# 06-General_I2C_Devices.net
KiCad netlist of a schematic drawn in Altium Designer
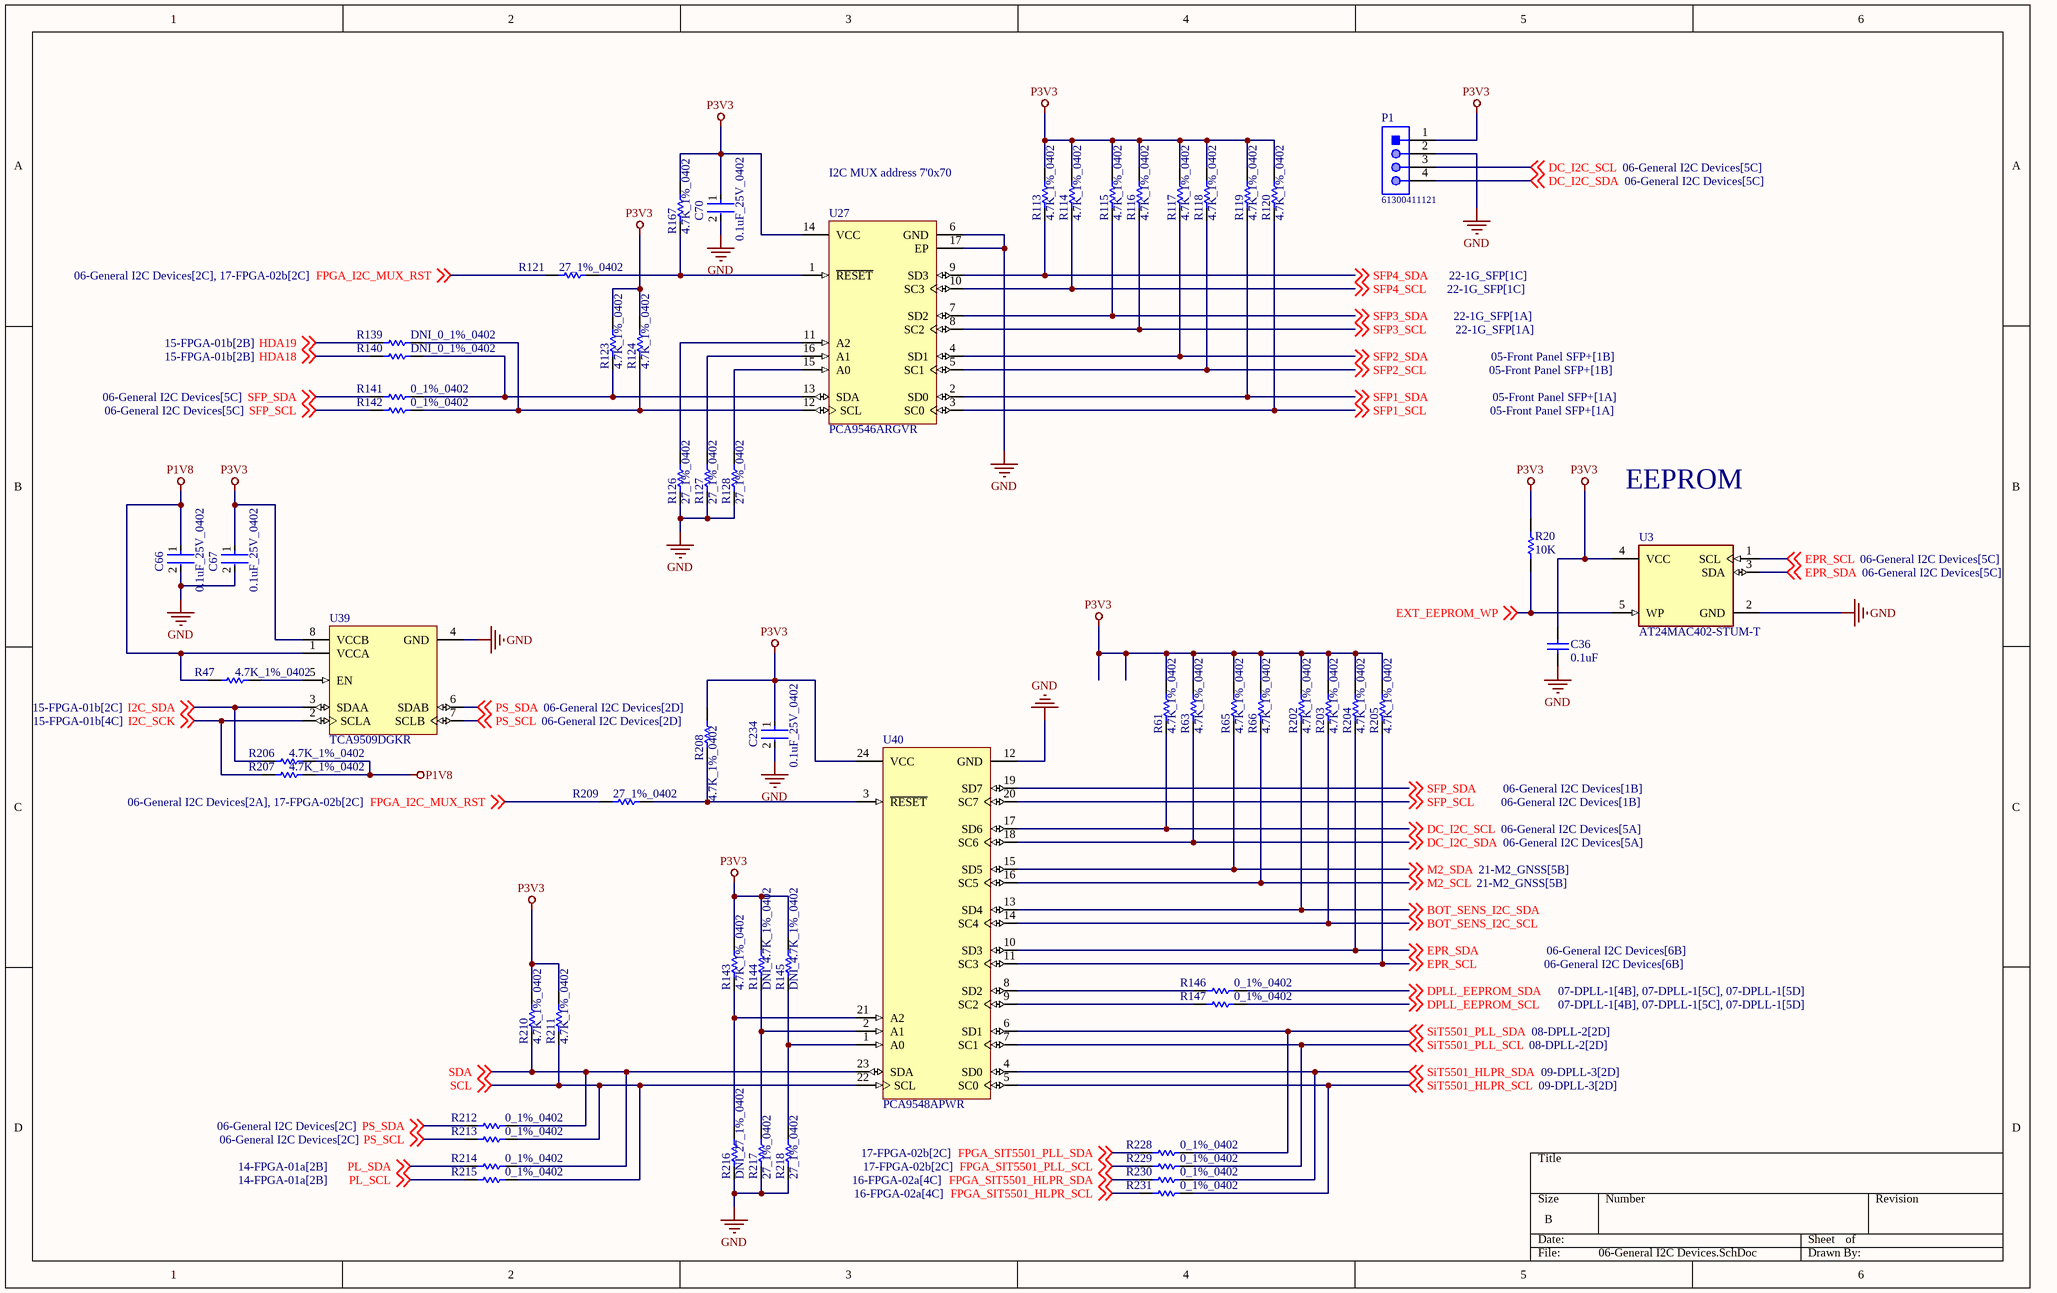
[diagram p0: 06-General I2C Devices.SchDoc]

(export (version "E")
  (design (tool "Eeschema 10.0.6"))
  (components
    (comp (ref "C36")
      (value "0.1uF")
      (footprint "CAPC1608X87X45ML20T05")
      (description "C0603X104K5RACAUTO")
      (fields (field (name "MANUFACTURER") "Kemet"))
      (libsource (lib "Altium Content Vault") (part "CAP"))
    )
    (comp (ref "C66")
      (value "0.1uF_25V_0402")
      (footprint "FP-0402-L_1_0_1-W_0_5_0_1-IPC_C")
      (description "General Purpose Ceramic Capacitor, 0402, 100nF, 10%, X7R, 15%, 25V")
      (fields (field (name "VOLTAGE") "25V") (field (name "TOLERANCE") "10%"))
      (libsource (lib "Altium Content Vault") (part "b4654b650e69147ec39a6b967a45e02"))
    )
    (comp (ref "C67")
      (value "0.1uF_25V_0402")
      (footprint "FP-0402-L_1_0_1-W_0_5_0_1-IPC_C")
      (description "General Purpose Ceramic Capacitor, 0402, 100nF, 10%, X7R, 15%, 25V")
      (fields (field (name "VOLTAGE") "25V") (field (name "TOLERANCE") "10%"))
      (libsource (lib "Altium Content Vault") (part "b4654b650e69147ec39a6b967a45e02"))
    )
    (comp (ref "C70")
      (value "0.1uF_25V_0402")
      (footprint "FP-0402-L_1_0_1-W_0_5_0_1-IPC_C")
      (description "General Purpose Ceramic Capacitor, 0402, 100nF, 10%, X7R, 15%, 25V")
      (fields (field (name "VOLTAGE") "25V") (field (name "TOLERANCE") "10%"))
      (libsource (lib "Altium Content Vault") (part "b4654b650e69147ec39a6b967a45e02"))
    )
    (comp (ref "C234")
      (value "0.1uF_25V_0402")
      (footprint "FP-0402-L_1_0_1-W_0_5_0_1-IPC_C")
      (description "General Purpose Ceramic Capacitor, 0402, 100nF, 10%, X7R, 15%, 25V")
      (fields (field (name "VOLTAGE") "25V") (field (name "TOLERANCE") "10%"))
      (libsource (lib "Altium Content Vault") (part "b4654b650e69147ec39a6b967a45e02"))
    )
    (comp (ref "P1")
      (value "61300411121")
      (footprint "61300411121")
      (description "THT Vertical Pin Header WR-PHD, Pitch 2.54 mm, Single Row, 4 pins")
      (fields (field (name "MANUFACTURER") "Wurth Elektronik") (field (name "PUBLISHER") "WurthElektronik"))
      (libsource (lib "Altium Content Vault") (part "WE-CN-1P-M-R4"))
    )
    (comp (ref "R20")
      (value "10K")
      (footprint "RESC1608X55X30LL15T20")
      (fields (field (name "TOLERANCE") "±1%") (field (name "MANUFACTURER") "Stackpole-Electronics-Inc."))
      (libsource (lib "Altium Content Vault") (part "RES-2"))
    )
    (comp (ref "R47")
      (value "4.7K_1%_0402")
      (footprint "RESC1005X40X25NL10T10")
      (fields (field (name "MANUFACTURER") "Bourns") (field (name "PART NUMBER") "CR0402-FX-4701GLF"))
      (libsource (lib "Altium Content Vault") (part "RES"))
    )
    (comp (ref "R61")
      (value "4.7K_1%_0402")
      (footprint "RESC1005X40X25NL10T10")
      (fields (field (name "MANUFACTURER") "Bourns") (field (name "PART NUMBER") "CR0402-FX-4701GLF"))
      (libsource (lib "Altium Content Vault") (part "RES"))
    )
    (comp (ref "R63")
      (value "4.7K_1%_0402")
      (footprint "RESC1005X40X25NL10T10")
      (fields (field (name "MANUFACTURER") "Bourns") (field (name "PART NUMBER") "CR0402-FX-4701GLF"))
      (libsource (lib "Altium Content Vault") (part "RES"))
    )
    (comp (ref "R65")
      (value "4.7K_1%_0402")
      (footprint "RESC1005X40X25NL10T10")
      (fields (field (name "MANUFACTURER") "Bourns") (field (name "PART NUMBER") "CR0402-FX-4701GLF"))
      (libsource (lib "Altium Content Vault") (part "RES"))
    )
    (comp (ref "R66")
      (value "4.7K_1%_0402")
      (footprint "RESC1005X40X25NL10T10")
      (fields (field (name "MANUFACTURER") "Bourns") (field (name "PART NUMBER") "CR0402-FX-4701GLF"))
      (libsource (lib "Altium Content Vault") (part "RES"))
    )
    (comp (ref "R113")
      (value "4.7K_1%_0402")
      (footprint "RESC1005X40X25NL10T10")
      (fields (field (name "MANUFACTURER") "Bourns") (field (name "PART NUMBER") "CR0402-FX-4701GLF"))
      (libsource (lib "Altium Content Vault") (part "RES"))
    )
    (comp (ref "R114")
      (value "4.7K_1%_0402")
      (footprint "RESC1005X40X25NL10T10")
      (fields (field (name "MANUFACTURER") "Bourns") (field (name "PART NUMBER") "CR0402-FX-4701GLF"))
      (libsource (lib "Altium Content Vault") (part "RES"))
    )
    (comp (ref "R115")
      (value "4.7K_1%_0402")
      (footprint "RESC1005X40X25NL10T10")
      (fields (field (name "MANUFACTURER") "Bourns") (field (name "PART NUMBER") "CR0402-FX-4701GLF"))
      (libsource (lib "Altium Content Vault") (part "RES"))
    )
    (comp (ref "R116")
      (value "4.7K_1%_0402")
      (footprint "RESC1005X40X25NL10T10")
      (fields (field (name "MANUFACTURER") "Bourns") (field (name "PART NUMBER") "CR0402-FX-4701GLF"))
      (libsource (lib "Altium Content Vault") (part "RES"))
    )
    (comp (ref "R117")
      (value "4.7K_1%_0402")
      (footprint "RESC1005X40X25NL10T10")
      (fields (field (name "MANUFACTURER") "Bourns") (field (name "PART NUMBER") "CR0402-FX-4701GLF"))
      (libsource (lib "Altium Content Vault") (part "RES"))
    )
    (comp (ref "R118")
      (value "4.7K_1%_0402")
      (footprint "RESC1005X40X25NL10T10")
      (fields (field (name "MANUFACTURER") "Bourns") (field (name "PART NUMBER") "CR0402-FX-4701GLF"))
      (libsource (lib "Altium Content Vault") (part "RES"))
    )
    (comp (ref "R119")
      (value "4.7K_1%_0402")
      (footprint "RESC1005X40X25NL10T10")
      (fields (field (name "MANUFACTURER") "Bourns") (field (name "PART NUMBER") "CR0402-FX-4701GLF"))
      (libsource (lib "Altium Content Vault") (part "RES"))
    )
    (comp (ref "R120")
      (value "4.7K_1%_0402")
      (footprint "RESC1005X40X25NL10T10")
      (fields (field (name "MANUFACTURER") "Bourns") (field (name "PART NUMBER") "CR0402-FX-4701GLF"))
      (libsource (lib "Altium Content Vault") (part "RES"))
    )
    (comp (ref "R121")
      (value "27_1%_0402")
      (footprint "RESC1005X40X25NL05T05")
      (fields (field (name "PART NUMBER") "CRCW040227R0FKED") (field (name "MANUFACTURER") "Vishay Dale"))
      (libsource (lib "Altium Content Vault") (part "RES"))
    )
    (comp (ref "R123")
      (value "4.7K_1%_0402")
      (footprint "RESC1005X40X25NL10T10")
      (fields (field (name "MANUFACTURER") "Bourns") (field (name "PART NUMBER") "CR0402-FX-4701GLF"))
      (libsource (lib "Altium Content Vault") (part "RES"))
    )
    (comp (ref "R124")
      (value "4.7K_1%_0402")
      (footprint "RESC1005X40X25NL10T10")
      (fields (field (name "MANUFACTURER") "Bourns") (field (name "PART NUMBER") "CR0402-FX-4701GLF"))
      (libsource (lib "Altium Content Vault") (part "RES"))
    )
    (comp (ref "R126")
      (value "27_1%_0402")
      (footprint "RESC1005X40X25NL05T05")
      (fields (field (name "PART NUMBER") "CRCW040227R0FKED") (field (name "MANUFACTURER") "Vishay Dale"))
      (libsource (lib "Altium Content Vault") (part "RES"))
    )
    (comp (ref "R127")
      (value "27_1%_0402")
      (footprint "RESC1005X40X25NL05T05")
      (fields (field (name "PART NUMBER") "CRCW040227R0FKED") (field (name "MANUFACTURER") "Vishay Dale"))
      (libsource (lib "Altium Content Vault") (part "RES"))
    )
    (comp (ref "R128")
      (value "27_1%_0402")
      (footprint "RESC1005X40X25NL05T05")
      (fields (field (name "PART NUMBER") "CRCW040227R0FKED") (field (name "MANUFACTURER") "Vishay Dale"))
      (libsource (lib "Altium Content Vault") (part "RES"))
    )
    (comp (ref "R139")
      (value "DNI_0_1%_0402")
      (footprint "RESC1005X40X25LL05T05")
      (description "Chip Resistor, 0 Ohm, 0.1 W, -55 to 155 degC, 0402 (1005 Metric), RoHS, Tape and Reel")
      (fields (field (name "MANUFACTURER") "Panasonic") (field (name "TOLERANCE") "5%"))
      (libsource (lib "Altium Content Vault") (part "RES-2"))
    )
    (comp (ref "R140")
      (value "DNI_0_1%_0402")
      (footprint "RESC1005X40X25LL05T05")
      (description "Chip Resistor, 0 Ohm, 0.1 W, -55 to 155 degC, 0402 (1005 Metric), RoHS, Tape and Reel")
      (fields (field (name "MANUFACTURER") "Panasonic") (field (name "TOLERANCE") "5%"))
      (libsource (lib "Altium Content Vault") (part "RES-2"))
    )
    (comp (ref "R141")
      (value "0_1%_0402")
      (footprint "RESC1005X40X25LL05T05")
      (description "Chip Resistor, 0 Ohm, 0.1 W, -55 to 155 degC, 0402 (1005 Metric), RoHS, Tape and Reel")
      (fields (field (name "MANUFACTURER") "Panasonic") (field (name "TOLERANCE") "5%"))
      (libsource (lib "Altium Content Vault") (part "RES-2"))
    )
    (comp (ref "R142")
      (value "0_1%_0402")
      (footprint "RESC1005X40X25LL05T05")
      (description "Chip Resistor, 0 Ohm, 0.1 W, -55 to 155 degC, 0402 (1005 Metric), RoHS, Tape and Reel")
      (fields (field (name "MANUFACTURER") "Panasonic") (field (name "TOLERANCE") "5%"))
      (libsource (lib "Altium Content Vault") (part "RES-2"))
    )
    (comp (ref "R143")
      (value "4.7K_1%_0402")
      (footprint "RESC1005X40X25NL10T10")
      (fields (field (name "MANUFACTURER") "Bourns") (field (name "PART NUMBER") "CR0402-FX-4701GLF"))
      (libsource (lib "Altium Content Vault") (part "RES"))
    )
    (comp (ref "R144")
      (value "DNI_4.7K_1%_0402")
      (footprint "RESC1005X40X25NL10T10")
      (fields (field (name "MANUFACTURER") "Bourns") (field (name "PART NUMBER") "CR0402-FX-4701GLF"))
      (libsource (lib "Altium Content Vault") (part "RES"))
    )
    (comp (ref "R145")
      (value "DNI_4.7K_1%_0402")
      (footprint "RESC1005X40X25NL10T10")
      (fields (field (name "MANUFACTURER") "Bourns") (field (name "PART NUMBER") "CR0402-FX-4701GLF"))
      (libsource (lib "Altium Content Vault") (part "RES"))
    )
    (comp (ref "R146")
      (value "0_1%_0402")
      (footprint "RESC1005X40X25LL05T05")
      (description "Chip Resistor, 0 Ohm, 0.1 W, -55 to 155 degC, 0402 (1005 Metric), RoHS, Tape and Reel")
      (fields (field (name "MANUFACTURER") "Panasonic") (field (name "TOLERANCE") "5%"))
      (libsource (lib "Altium Content Vault") (part "RES-2"))
    )
    (comp (ref "R147")
      (value "0_1%_0402")
      (footprint "RESC1005X40X25LL05T05")
      (description "Chip Resistor, 0 Ohm, 0.1 W, -55 to 155 degC, 0402 (1005 Metric), RoHS, Tape and Reel")
      (fields (field (name "MANUFACTURER") "Panasonic") (field (name "TOLERANCE") "5%"))
      (libsource (lib "Altium Content Vault") (part "RES-2"))
    )
    (comp (ref "R167")
      (value "4.7K_1%_0402")
      (footprint "RESC1005X40X25NL10T10")
      (fields (field (name "MANUFACTURER") "Bourns") (field (name "PART NUMBER") "CR0402-FX-4701GLF"))
      (libsource (lib "Altium Content Vault") (part "RES"))
    )
    (comp (ref "R202")
      (value "4.7K_1%_0402")
      (footprint "RESC1005X40X25NL10T10")
      (fields (field (name "MANUFACTURER") "Bourns") (field (name "PART NUMBER") "CR0402-FX-4701GLF"))
      (libsource (lib "Altium Content Vault") (part "RES"))
    )
    (comp (ref "R203")
      (value "4.7K_1%_0402")
      (footprint "RESC1005X40X25NL10T10")
      (fields (field (name "MANUFACTURER") "Bourns") (field (name "PART NUMBER") "CR0402-FX-4701GLF"))
      (libsource (lib "Altium Content Vault") (part "RES"))
    )
    (comp (ref "R204")
      (value "4.7K_1%_0402")
      (footprint "RESC1005X40X25NL10T10")
      (fields (field (name "MANUFACTURER") "Bourns") (field (name "PART NUMBER") "CR0402-FX-4701GLF"))
      (libsource (lib "Altium Content Vault") (part "RES"))
    )
    (comp (ref "R205")
      (value "4.7K_1%_0402")
      (footprint "RESC1005X40X25NL10T10")
      (fields (field (name "MANUFACTURER") "Bourns") (field (name "PART NUMBER") "CR0402-FX-4701GLF"))
      (libsource (lib "Altium Content Vault") (part "RES"))
    )
    (comp (ref "R206")
      (value "4.7K_1%_0402")
      (footprint "RESC1005X40X25NL10T10")
      (fields (field (name "MANUFACTURER") "Bourns") (field (name "PART NUMBER") "CR0402-FX-4701GLF"))
      (libsource (lib "Altium Content Vault") (part "RES"))
    )
    (comp (ref "R207")
      (value "4.7K_1%_0402")
      (footprint "RESC1005X40X25NL10T10")
      (fields (field (name "MANUFACTURER") "Bourns") (field (name "PART NUMBER") "CR0402-FX-4701GLF"))
      (libsource (lib "Altium Content Vault") (part "RES"))
    )
    (comp (ref "R208")
      (value "4.7K_1%_0402")
      (footprint "RESC1005X40X25NL10T10")
      (fields (field (name "MANUFACTURER") "Bourns") (field (name "PART NUMBER") "CR0402-FX-4701GLF"))
      (libsource (lib "Altium Content Vault") (part "RES"))
    )
    (comp (ref "R209")
      (value "27_1%_0402")
      (footprint "RESC1005X40X25NL05T05")
      (fields (field (name "PART NUMBER") "CRCW040227R0FKED") (field (name "MANUFACTURER") "Vishay Dale"))
      (libsource (lib "Altium Content Vault") (part "RES"))
    )
    (comp (ref "R210")
      (value "4.7K_1%_0402")
      (footprint "RESC1005X40X25NL10T10")
      (fields (field (name "MANUFACTURER") "Bourns") (field (name "PART NUMBER") "CR0402-FX-4701GLF"))
      (libsource (lib "Altium Content Vault") (part "RES"))
    )
    (comp (ref "R211")
      (value "4.7K_1%_0402")
      (footprint "RESC1005X40X25NL10T10")
      (fields (field (name "MANUFACTURER") "Bourns") (field (name "PART NUMBER") "CR0402-FX-4701GLF"))
      (libsource (lib "Altium Content Vault") (part "RES"))
    )
    (comp (ref "R212")
      (value "0_1%_0402")
      (footprint "RESC1005X40X25LL05T05")
      (description "Chip Resistor, 0 Ohm, 0.1 W, -55 to 155 degC, 0402 (1005 Metric), RoHS, Tape and Reel")
      (fields (field (name "MANUFACTURER") "Panasonic") (field (name "TOLERANCE") "5%"))
      (libsource (lib "Altium Content Vault") (part "RES-2"))
    )
    (comp (ref "R213")
      (value "0_1%_0402")
      (footprint "RESC1005X40X25LL05T05")
      (description "Chip Resistor, 0 Ohm, 0.1 W, -55 to 155 degC, 0402 (1005 Metric), RoHS, Tape and Reel")
      (fields (field (name "MANUFACTURER") "Panasonic") (field (name "TOLERANCE") "5%"))
      (libsource (lib "Altium Content Vault") (part "RES-2"))
    )
    (comp (ref "R214")
      (value "0_1%_0402")
      (footprint "RESC1005X40X25LL05T05")
      (description "Chip Resistor, 0 Ohm, 0.1 W, -55 to 155 degC, 0402 (1005 Metric), RoHS, Tape and Reel")
      (fields (field (name "MANUFACTURER") "Panasonic") (field (name "TOLERANCE") "5%"))
      (libsource (lib "Altium Content Vault") (part "RES-2"))
    )
    (comp (ref "R215")
      (value "0_1%_0402")
      (footprint "RESC1005X40X25LL05T05")
      (description "Chip Resistor, 0 Ohm, 0.1 W, -55 to 155 degC, 0402 (1005 Metric), RoHS, Tape and Reel")
      (fields (field (name "MANUFACTURER") "Panasonic") (field (name "TOLERANCE") "5%"))
      (libsource (lib "Altium Content Vault") (part "RES-2"))
    )
    (comp (ref "R216")
      (value "DNI_27_1%_0402")
      (footprint "RESC1005X40X25NL05T05")
      (fields (field (name "PART NUMBER") "CRCW040227R0FKED") (field (name "MANUFACTURER") "Vishay Dale"))
      (libsource (lib "Altium Content Vault") (part "RES"))
    )
    (comp (ref "R217")
      (value "27_1%_0402")
      (footprint "RESC1005X40X25NL05T05")
      (fields (field (name "PART NUMBER") "CRCW040227R0FKED") (field (name "MANUFACTURER") "Vishay Dale"))
      (libsource (lib "Altium Content Vault") (part "RES"))
    )
    (comp (ref "R218")
      (value "27_1%_0402")
      (footprint "RESC1005X40X25NL05T05")
      (fields (field (name "PART NUMBER") "CRCW040227R0FKED") (field (name "MANUFACTURER") "Vishay Dale"))
      (libsource (lib "Altium Content Vault") (part "RES"))
    )
    (comp (ref "R228")
      (value "0_1%_0402")
      (footprint "RESC1005X40X25LL05T05")
      (description "Chip Resistor, 0 Ohm, 0.1 W, -55 to 155 degC, 0402 (1005 Metric), RoHS, Tape and Reel")
      (fields (field (name "MANUFACTURER") "Panasonic") (field (name "TOLERANCE") "5%"))
      (libsource (lib "Altium Content Vault") (part "RES-2"))
    )
    (comp (ref "R229")
      (value "0_1%_0402")
      (footprint "RESC1005X40X25LL05T05")
      (description "Chip Resistor, 0 Ohm, 0.1 W, -55 to 155 degC, 0402 (1005 Metric), RoHS, Tape and Reel")
      (fields (field (name "MANUFACTURER") "Panasonic") (field (name "TOLERANCE") "5%"))
      (libsource (lib "Altium Content Vault") (part "RES-2"))
    )
    (comp (ref "R230")
      (value "0_1%_0402")
      (footprint "RESC1005X40X25LL05T05")
      (description "Chip Resistor, 0 Ohm, 0.1 W, -55 to 155 degC, 0402 (1005 Metric), RoHS, Tape and Reel")
      (fields (field (name "MANUFACTURER") "Panasonic") (field (name "TOLERANCE") "5%"))
      (libsource (lib "Altium Content Vault") (part "RES-2"))
    )
    (comp (ref "R231")
      (value "0_1%_0402")
      (footprint "RESC1005X40X25LL05T05")
      (description "Chip Resistor, 0 Ohm, 0.1 W, -55 to 155 degC, 0402 (1005 Metric), RoHS, Tape and Reel")
      (fields (field (name "MANUFACTURER") "Panasonic") (field (name "TOLERANCE") "5%"))
      (libsource (lib "Altium Content Vault") (part "RES-2"))
    )
    (comp (ref "U3")
      (value "AT24MAC402-STUM-T")
      (footprint "FP-5TS1-IPC_C")
      (description "IC EEPROM 2K I2C 1MHZ SOT23-5")
      (fields
        (field (name "MANUFACTURER") "Microchip")
        (field (name "OCTOPART") "https://octopart.com/at24mac402-stum-t-microchip-77758112")
      )
      (libsource (lib "Altium Content Vault") (part "93fe34f5f049140596bab6421a6454b"))
    )
    (comp (ref "U27")
      (value "PCA9546ARGVR")
      (footprint "RGV0016A_V")
      (fields (field (name "MANUFACTURER") "Texas Instruments"))
      (libsource (lib "Altium Content Vault") (part "TI-PCA9546A-VQFN_RGV-16"))
    )
    (comp (ref "U39")
      (value "TCA9509DGKR")
      (footprint "DGK0008A_L")
      (fields (field (name "MANUFACTURER") "Texas Instruments"))
      (libsource (lib "Altium Content Vault") (part "TI-TCA9509-MSOP_DGK-8"))
    )
    (comp (ref "U40")
      (value "PCA9548APWR")
      (footprint "PW0024A_N")
      (fields (field (name "MANUFACTURER") "Texas Instruments"))
      (libsource (lib "Altium Content Vault") (part "TI-PCA9548A-TSSOP_PW-24"))
    )
  )
  (nets
    (net (code "1") (name "BOT_SENS_I2C_SCL") (class "Default")
      (node (ref "R203") (pin "1") (pinfunction "1_1") (pintype "passive"))
      (node (ref "U40") (pin "14") (pinfunction "SC4_14") (pintype "bidirectional"))
    )
    (net (code "2") (name "BOT_SENS_I2C_SDA") (class "Default")
      (node (ref "R202") (pin "1") (pinfunction "1_1") (pintype "passive"))
      (node (ref "U40") (pin "13") (pinfunction "SD4_13") (pintype "bidirectional"))
    )
    (net (code "3") (name "DC_I2C_SCL") (class "Default")
      (node (ref "P1") (pin "3") (pinfunction "3_3") (pintype "passive"))
      (node (ref "R61") (pin "1") (pinfunction "1_1") (pintype "passive"))
      (node (ref "U40") (pin "17") (pinfunction "SD6_17") (pintype "bidirectional"))
    )
    (net (code "4") (name "DC_I2C_SDA") (class "Default")
      (node (ref "P1") (pin "4") (pinfunction "4_4") (pintype "passive"))
      (node (ref "R63") (pin "1") (pinfunction "1_1") (pintype "passive"))
      (node (ref "U40") (pin "18") (pinfunction "SC6_18") (pintype "bidirectional"))
    )
    (net (code "5") (name "DPLL_EEPROM_SCL") (class "Default")
      (node (ref "R147") (pin "2") (pinfunction "2_2") (pintype "passive"))
    )
    (net (code "6") (name "DPLL_EEPROM_SDA") (class "Default")
      (node (ref "R146") (pin "2") (pinfunction "2_2") (pintype "passive"))
    )
    (net (code "7") (name "EPR_SCL") (class "Default")
      (node (ref "R205") (pin "1") (pinfunction "1_1") (pintype "passive"))
      (node (ref "U3") (pin "1") (pinfunction "SCL_1") (pintype "input"))
      (node (ref "U40") (pin "11") (pinfunction "SC3_11") (pintype "bidirectional"))
    )
    (net (code "8") (name "EPR_SDA") (class "Default")
      (node (ref "R204") (pin "1") (pinfunction "1_1") (pintype "passive"))
      (node (ref "U3") (pin "3") (pinfunction "SDA_3") (pintype "bidirectional"))
      (node (ref "U40") (pin "10") (pinfunction "SD3_10") (pintype "bidirectional"))
    )
    (net (code "9") (name "EXT_EEPROM_WP") (class "Default")
      (node (ref "R20") (pin "1") (pinfunction "1_1") (pintype "passive"))
      (node (ref "U3") (pin "5") (pinfunction "WP_5") (pintype "input"))
    )
    (net (code "10") (name "FPGA_I2C_MUX_RST") (class "Default")
      (node (ref "R121") (pin "1") (pinfunction "1_1") (pintype "passive"))
      (node (ref "R209") (pin "1") (pinfunction "1_1") (pintype "passive"))
    )
    (net (code "11") (name "FPGA_SIT5501_HLPR_SCL") (class "Default")
      (node (ref "R231") (pin "1") (pinfunction "1_1") (pintype "passive"))
    )
    (net (code "12") (name "FPGA_SIT5501_HLPR_SDA") (class "Default")
      (node (ref "R230") (pin "1") (pinfunction "1_1") (pintype "passive"))
    )
    (net (code "13") (name "FPGA_SIT5501_PLL_SCL") (class "Default")
      (node (ref "R229") (pin "1") (pinfunction "1_1") (pintype "passive"))
    )
    (net (code "14") (name "FPGA_SIT5501_PLL_SDA") (class "Default")
      (node (ref "R228") (pin "1") (pinfunction "1_1") (pintype "passive"))
    )
    (net (code "15") (name "GND") (class "Default")
      (node (ref "C234") (pin "2") (pinfunction "2_2") (pintype "passive"))
      (node (ref "C36") (pin "1") (pinfunction "1_1") (pintype "passive"))
      (node (ref "C66") (pin "2") (pinfunction "2_2") (pintype "passive"))
      (node (ref "C67") (pin "2") (pinfunction "2_2") (pintype "passive"))
      (node (ref "C70") (pin "2") (pinfunction "2_2") (pintype "passive"))
      (node (ref "P1") (pin "2") (pinfunction "2_2") (pintype "passive"))
      (node (ref "R126") (pin "1") (pinfunction "1_1") (pintype "passive"))
      (node (ref "R127") (pin "1") (pinfunction "1_1") (pintype "passive"))
      (node (ref "R128") (pin "1") (pinfunction "1_1") (pintype "passive"))
      (node (ref "R216") (pin "1") (pinfunction "1_1") (pintype "passive"))
      (node (ref "R217") (pin "1") (pinfunction "1_1") (pintype "passive"))
      (node (ref "R218") (pin "1") (pinfunction "1_1") (pintype "passive"))
      (node (ref "U27") (pin "17") (pinfunction "EP_17") (pintype "passive"))
      (node (ref "U27") (pin "6") (pinfunction "GND_6") (pintype "power_in"))
      (node (ref "U3") (pin "2") (pinfunction "GND_2") (pintype "power_in"))
      (node (ref "U39") (pin "4") (pinfunction "GND_4") (pintype "power_in"))
      (node (ref "U40") (pin "12") (pinfunction "GND_12") (pintype "power_in"))
    )
    (net (code "16") (name "HDA18") (class "Default")
      (node (ref "R140") (pin "1") (pinfunction "1_1") (pintype "passive"))
    )
    (net (code "17") (name "HDA19") (class "Default")
      (node (ref "R139") (pin "1") (pinfunction "1_1") (pintype "passive"))
    )
    (net (code "18") (name "I2C_SCK") (class "Default")
      (node (ref "R207") (pin "2") (pinfunction "2_2") (pintype "passive"))
      (node (ref "U39") (pin "2") (pinfunction "SCLA_2") (pintype "bidirectional"))
    )
    (net (code "19") (name "I2C_SDA") (class "Default")
      (node (ref "R206") (pin "2") (pinfunction "2_2") (pintype "passive"))
      (node (ref "U39") (pin "3") (pinfunction "SDAA_3") (pintype "bidirectional"))
    )
    (net (code "20") (name "M2_SCL") (class "Default")
      (node (ref "R66") (pin "1") (pinfunction "1_1") (pintype "passive"))
      (node (ref "U40") (pin "16") (pinfunction "SC5_16") (pintype "bidirectional"))
    )
    (net (code "21") (name "M2_SDA") (class "Default")
      (node (ref "R65") (pin "1") (pinfunction "1_1") (pintype "passive"))
      (node (ref "U40") (pin "15") (pinfunction "SD5_15") (pintype "bidirectional"))
    )
    (net (code "22") (name "Net-(U27-A0)") (class "Default")
      (node (ref "R128") (pin "2") (pinfunction "2_2") (pintype "passive"))
      (node (ref "U27") (pin "15") (pinfunction "A0_15") (pintype "input"))
    )
    (net (code "23") (name "Net-(U27-A1)") (class "Default")
      (node (ref "R127") (pin "2") (pinfunction "2_2") (pintype "passive"))
      (node (ref "U27") (pin "16") (pinfunction "A1_16") (pintype "input"))
    )
    (net (code "24") (name "Net-(U27-A2)") (class "Default")
      (node (ref "R126") (pin "2") (pinfunction "2_2") (pintype "passive"))
      (node (ref "U27") (pin "11") (pinfunction "A2_11") (pintype "input"))
    )
    (net (code "25") (name "Net-(U27-SCL)") (class "Default")
      (node (ref "R124") (pin "1") (pinfunction "1_1") (pintype "passive"))
      (node (ref "R139") (pin "2") (pinfunction "2_2") (pintype "passive"))
      (node (ref "R142") (pin "2") (pinfunction "2_2") (pintype "passive"))
      (node (ref "U27") (pin "12") (pinfunction "SCL_12") (pintype "bidirectional"))
    )
    (net (code "26") (name "Net-(U27-SDA)") (class "Default")
      (node (ref "R123") (pin "1") (pinfunction "1_1") (pintype "passive"))
      (node (ref "R140") (pin "2") (pinfunction "2_2") (pintype "passive"))
      (node (ref "R141") (pin "2") (pinfunction "2_2") (pintype "passive"))
      (node (ref "U27") (pin "13") (pinfunction "SDA_13") (pintype "bidirectional"))
    )
    (net (code "27") (name "Net-(U27-~{RESET})") (class "Default")
      (node (ref "R121") (pin "2") (pinfunction "2_2") (pintype "passive"))
      (node (ref "R167") (pin "1") (pinfunction "1_1") (pintype "passive"))
      (node (ref "U27") (pin "1") (pinfunction "~{RESET}_1") (pintype "input"))
    )
    (net (code "28") (name "Net-(U39-EN)") (class "Default")
      (node (ref "R47") (pin "1") (pinfunction "1_1") (pintype "passive"))
      (node (ref "U39") (pin "5") (pinfunction "EN_5") (pintype "input"))
    )
    (net (code "29") (name "Net-(U40-A0)") (class "Default")
      (node (ref "R145") (pin "1") (pinfunction "1_1") (pintype "passive"))
      (node (ref "R218") (pin "2") (pinfunction "2_2") (pintype "passive"))
      (node (ref "U40") (pin "1") (pinfunction "A0_1") (pintype "input"))
    )
    (net (code "30") (name "Net-(U40-A1)") (class "Default")
      (node (ref "R144") (pin "1") (pinfunction "1_1") (pintype "passive"))
      (node (ref "R217") (pin "2") (pinfunction "2_2") (pintype "passive"))
      (node (ref "U40") (pin "2") (pinfunction "A1_2") (pintype "input"))
    )
    (net (code "31") (name "Net-(U40-A2)") (class "Default")
      (node (ref "R143") (pin "1") (pinfunction "1_1") (pintype "passive"))
      (node (ref "R216") (pin "2") (pinfunction "2_2") (pintype "passive"))
      (node (ref "U40") (pin "21") (pinfunction "A2_21") (pintype "input"))
    )
    (net (code "32") (name "Net-(U40-SC2)") (class "Default")
      (node (ref "R147") (pin "1") (pinfunction "1_1") (pintype "passive"))
      (node (ref "U40") (pin "9") (pinfunction "SC2_9") (pintype "bidirectional"))
    )
    (net (code "33") (name "Net-(U40-SD2)") (class "Default")
      (node (ref "R146") (pin "1") (pinfunction "1_1") (pintype "passive"))
      (node (ref "U40") (pin "8") (pinfunction "SD2_8") (pintype "bidirectional"))
    )
    (net (code "34") (name "Net-(U40-~{RESET})") (class "Default")
      (node (ref "R208") (pin "1") (pinfunction "1_1") (pintype "passive"))
      (node (ref "R209") (pin "2") (pinfunction "2_2") (pintype "passive"))
      (node (ref "U40") (pin "3") (pinfunction "~{RESET}_3") (pintype "input"))
    )
    (net (code "35") (name "P1V8") (class "Default")
      (node (ref "C66") (pin "1") (pinfunction "1_1") (pintype "passive"))
      (node (ref "R206") (pin "1") (pinfunction "1_1") (pintype "passive"))
      (node (ref "R207") (pin "1") (pinfunction "1_1") (pintype "passive"))
      (node (ref "R47") (pin "2") (pinfunction "2_2") (pintype "passive"))
      (node (ref "U39") (pin "1") (pinfunction "VCCA_1") (pintype "power_in"))
    )
    (net (code "36") (name "P3V3") (class "Default")
      (node (ref "C234") (pin "1") (pinfunction "1_1") (pintype "passive"))
      (node (ref "C36") (pin "2") (pinfunction "2_2") (pintype "passive"))
      (node (ref "C67") (pin "1") (pinfunction "1_1") (pintype "passive"))
      (node (ref "C70") (pin "1") (pinfunction "1_1") (pintype "passive"))
      (node (ref "P1") (pin "1") (pinfunction "1_1") (pintype "passive"))
      (node (ref "R113") (pin "2") (pinfunction "2_2") (pintype "passive"))
      (node (ref "R114") (pin "2") (pinfunction "2_2") (pintype "passive"))
      (node (ref "R115") (pin "2") (pinfunction "2_2") (pintype "passive"))
      (node (ref "R116") (pin "2") (pinfunction "2_2") (pintype "passive"))
      (node (ref "R117") (pin "2") (pinfunction "2_2") (pintype "passive"))
      (node (ref "R118") (pin "2") (pinfunction "2_2") (pintype "passive"))
      (node (ref "R119") (pin "2") (pinfunction "2_2") (pintype "passive"))
      (node (ref "R120") (pin "2") (pinfunction "2_2") (pintype "passive"))
      (node (ref "R123") (pin "2") (pinfunction "2_2") (pintype "passive"))
      (node (ref "R124") (pin "2") (pinfunction "2_2") (pintype "passive"))
      (node (ref "R143") (pin "2") (pinfunction "2_2") (pintype "passive"))
      (node (ref "R144") (pin "2") (pinfunction "2_2") (pintype "passive"))
      (node (ref "R145") (pin "2") (pinfunction "2_2") (pintype "passive"))
      (node (ref "R167") (pin "2") (pinfunction "2_2") (pintype "passive"))
      (node (ref "R20") (pin "2") (pinfunction "2_2") (pintype "passive"))
      (node (ref "R202") (pin "2") (pinfunction "2_2") (pintype "passive"))
      (node (ref "R203") (pin "2") (pinfunction "2_2") (pintype "passive"))
      (node (ref "R204") (pin "2") (pinfunction "2_2") (pintype "passive"))
      (node (ref "R205") (pin "2") (pinfunction "2_2") (pintype "passive"))
      (node (ref "R208") (pin "2") (pinfunction "2_2") (pintype "passive"))
      (node (ref "R210") (pin "2") (pinfunction "2_2") (pintype "passive"))
      (node (ref "R211") (pin "2") (pinfunction "2_2") (pintype "passive"))
      (node (ref "R61") (pin "2") (pinfunction "2_2") (pintype "passive"))
      (node (ref "R63") (pin "2") (pinfunction "2_2") (pintype "passive"))
      (node (ref "R65") (pin "2") (pinfunction "2_2") (pintype "passive"))
      (node (ref "R66") (pin "2") (pinfunction "2_2") (pintype "passive"))
      (node (ref "U27") (pin "14") (pinfunction "VCC_14") (pintype "power_in"))
      (node (ref "U3") (pin "4") (pinfunction "VCC_4") (pintype "power_in"))
      (node (ref "U39") (pin "8") (pinfunction "VCCB_8") (pintype "power_in"))
      (node (ref "U40") (pin "24") (pinfunction "VCC_24") (pintype "power_in"))
    )
    (net (code "37") (name "PL_SCL") (class "Default")
      (node (ref "R215") (pin "1") (pinfunction "1_1") (pintype "passive"))
    )
    (net (code "38") (name "PL_SDA") (class "Default")
      (node (ref "R214") (pin "1") (pinfunction "1_1") (pintype "passive"))
    )
    (net (code "39") (name "PS_SCL") (class "Default")
      (node (ref "R213") (pin "1") (pinfunction "1_1") (pintype "passive"))
      (node (ref "U39") (pin "7") (pinfunction "SCLB_7") (pintype "bidirectional"))
    )
    (net (code "40") (name "PS_SDA") (class "Default")
      (node (ref "R212") (pin "1") (pinfunction "1_1") (pintype "passive"))
      (node (ref "U39") (pin "6") (pinfunction "SDAB_6") (pintype "bidirectional"))
    )
    (net (code "41") (name "SCL") (class "Default")
      (node (ref "R211") (pin "1") (pinfunction "1_1") (pintype "passive"))
      (node (ref "R213") (pin "2") (pinfunction "2_2") (pintype "passive"))
      (node (ref "R215") (pin "2") (pinfunction "2_2") (pintype "passive"))
      (node (ref "U40") (pin "22") (pinfunction "SCL_22") (pintype "input"))
    )
    (net (code "42") (name "SDA") (class "Default")
      (node (ref "R210") (pin "1") (pinfunction "1_1") (pintype "passive"))
      (node (ref "R212") (pin "2") (pinfunction "2_2") (pintype "passive"))
      (node (ref "R214") (pin "2") (pinfunction "2_2") (pintype "passive"))
      (node (ref "U40") (pin "23") (pinfunction "SDA_23") (pintype "bidirectional"))
    )
    (net (code "43") (name "SFP1_SCL") (class "Default")
      (node (ref "R120") (pin "1") (pinfunction "1_1") (pintype "passive"))
      (node (ref "U27") (pin "3") (pinfunction "SC0_3") (pintype "bidirectional"))
    )
    (net (code "44") (name "SFP1_SDA") (class "Default")
      (node (ref "R119") (pin "1") (pinfunction "1_1") (pintype "passive"))
      (node (ref "U27") (pin "2") (pinfunction "SD0_2") (pintype "bidirectional"))
    )
    (net (code "45") (name "SFP2_SCL") (class "Default")
      (node (ref "R118") (pin "1") (pinfunction "1_1") (pintype "passive"))
      (node (ref "U27") (pin "5") (pinfunction "SC1_5") (pintype "bidirectional"))
    )
    (net (code "46") (name "SFP2_SDA") (class "Default")
      (node (ref "R117") (pin "1") (pinfunction "1_1") (pintype "passive"))
      (node (ref "U27") (pin "4") (pinfunction "SD1_4") (pintype "bidirectional"))
    )
    (net (code "47") (name "SFP3_SCL") (class "Default")
      (node (ref "R116") (pin "1") (pinfunction "1_1") (pintype "passive"))
      (node (ref "U27") (pin "8") (pinfunction "SC2_8") (pintype "bidirectional"))
    )
    (net (code "48") (name "SFP3_SDA") (class "Default")
      (node (ref "R115") (pin "1") (pinfunction "1_1") (pintype "passive"))
      (node (ref "U27") (pin "7") (pinfunction "SD2_7") (pintype "bidirectional"))
    )
    (net (code "49") (name "SFP4_SCL") (class "Default")
      (node (ref "R114") (pin "1") (pinfunction "1_1") (pintype "passive"))
      (node (ref "U27") (pin "10") (pinfunction "SC3_10") (pintype "bidirectional"))
    )
    (net (code "50") (name "SFP4_SDA") (class "Default")
      (node (ref "R113") (pin "1") (pinfunction "1_1") (pintype "passive"))
      (node (ref "U27") (pin "9") (pinfunction "SD3_9") (pintype "bidirectional"))
    )
    (net (code "51") (name "SFP_SCL") (class "Default")
      (node (ref "R142") (pin "1") (pinfunction "1_1") (pintype "passive"))
      (node (ref "U40") (pin "20") (pinfunction "SC7_20") (pintype "bidirectional"))
    )
    (net (code "52") (name "SFP_SDA") (class "Default")
      (node (ref "R141") (pin "1") (pinfunction "1_1") (pintype "passive"))
      (node (ref "U40") (pin "19") (pinfunction "SD7_19") (pintype "bidirectional"))
    )
    (net (code "53") (name "SiT5501_HLPR_SCL") (class "Default")
      (node (ref "R231") (pin "2") (pinfunction "2_2") (pintype "passive"))
      (node (ref "U40") (pin "5") (pinfunction "SC0_5") (pintype "bidirectional"))
    )
    (net (code "54") (name "SiT5501_HLPR_SDA") (class "Default")
      (node (ref "R230") (pin "2") (pinfunction "2_2") (pintype "passive"))
      (node (ref "U40") (pin "4") (pinfunction "SD0_4") (pintype "bidirectional"))
    )
    (net (code "55") (name "SiT5501_PLL_SCL") (class "Default")
      (node (ref "R229") (pin "2") (pinfunction "2_2") (pintype "passive"))
      (node (ref "U40") (pin "7") (pinfunction "SC1_7") (pintype "bidirectional"))
    )
    (net (code "56") (name "SiT5501_PLL_SDA") (class "Default")
      (node (ref "R228") (pin "2") (pinfunction "2_2") (pintype "passive"))
      (node (ref "U40") (pin "6") (pinfunction "SD1_6") (pintype "bidirectional"))
    )
  )
)
